# TCAN330_PINOUT.net
KiCad netlist of a schematic drawn in Altium Designer
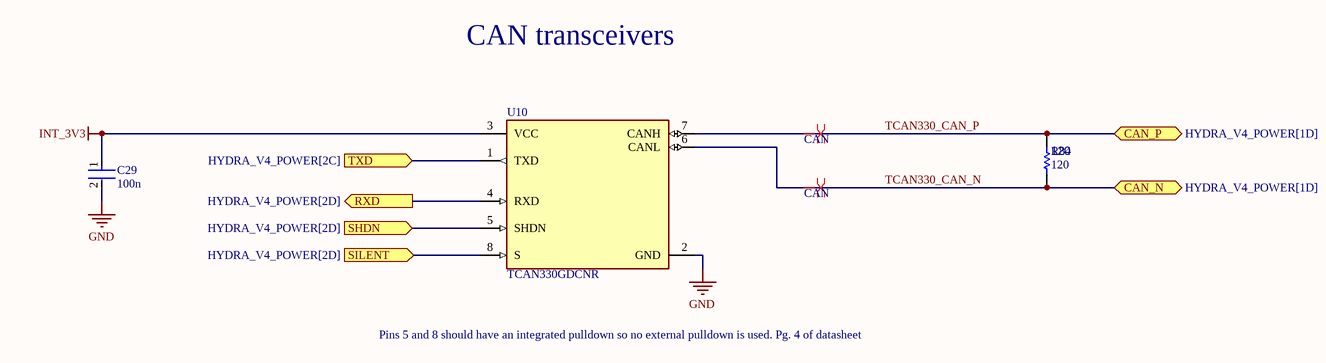
[diagram p0: TCAN330_PINOUT.SchDoc]

(export (version "E")
  (design (tool "Eeschema 10.0.6"))
  (components
    (comp (ref "C29")
      (value "100n")
      (footprint "FP-0402-L_1_0_0_05-W_0_5-IPC_A")
      (description "LARGE PADS, 0402 CAP, CHANGE COMMENT TO MATCH REAL P/N")
      (libsource (lib "Space Concordia") (part "b4654b650e69147ec39a6b967a45e02"))
    )
    (comp (ref "R84")
      (value "120")
      (footprint "R0603B")
      (description "Resistor")
      (fields (field (name "ALTIUM_VALUE") "120"))
      (libsource (lib "Space Concordia") (part "Resistor"))
    )
    (comp (ref "U10")
      (value "TCAN330GDCNR")
      (footprint "FP-DCN0008A-MFG")
      (description "IC TRANSCEIVER 1/1 SOT23-8")
      (libsource (lib "Altium Content Vault") (part "22681b49c22ad38c6a4e12e04c36c7a"))
    )
  )
  (nets
    (net (code "1") (name "/RXD") (class "Default")
      (node (ref "U10") (pin "4") (pinfunction "RXD_4") (pintype "input"))
    )
    (net (code "2") (name "/SHDN") (class "Default")
      (node (ref "U10") (pin "5") (pinfunction "SHDN_5") (pintype "input"))
    )
    (net (code "3") (name "/SILENT") (class "Default")
      (node (ref "U10") (pin "8") (pinfunction "S_8") (pintype "input"))
    )
    (net (code "4") (name "/TCAN330_CAN_N") (class "Default")
      (node (ref "R84") (pin "1") (pinfunction "1_1") (pintype "passive"))
      (node (ref "U10") (pin "6") (pinfunction "CANL_6") (pintype "bidirectional"))
    )
    (net (code "5") (name "/TCAN330_CAN_P") (class "Default")
      (node (ref "R84") (pin "2") (pinfunction "2_2") (pintype "passive"))
      (node (ref "U10") (pin "7") (pinfunction "CANH_7") (pintype "bidirectional"))
    )
    (net (code "6") (name "/TXD") (class "Default")
      (node (ref "U10") (pin "1") (pinfunction "TXD_1") (pintype "output"))
    )
    (net (code "7") (name "GND") (class "Default")
      (node (ref "C29") (pin "2") (pinfunction "2_2") (pintype "passive"))
      (node (ref "U10") (pin "2") (pinfunction "GND_2") (pintype "power_in"))
    )
    (net (code "8") (name "INT_3V3") (class "Default")
      (node (ref "C29") (pin "1") (pinfunction "1_1") (pintype "passive"))
      (node (ref "U10") (pin "3") (pinfunction "VCC_3") (pintype "power_in"))
    )
  )
)
